# POS5V.net
KiCad netlist of a schematic drawn in Altium Designer
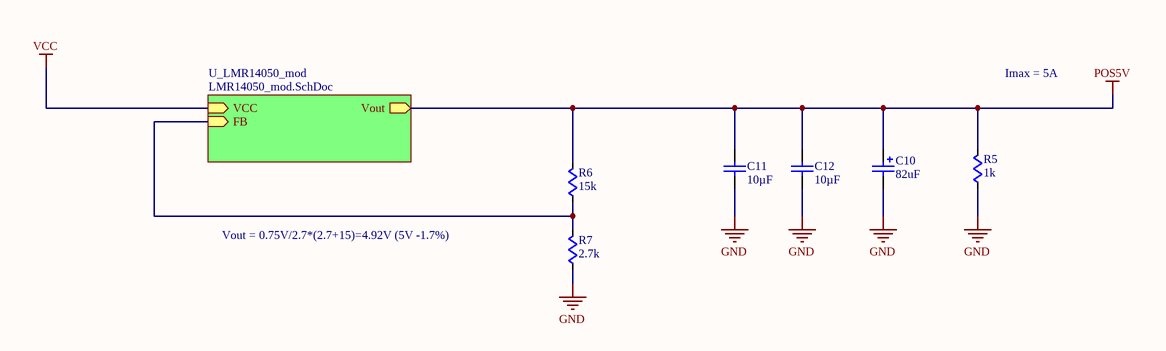
[diagram p0: POS5V.SchDoc]

(export (version "E")
  (design (tool "Eeschema 10.0.6"))
  (components
    (comp (ref "C10")
      (value "82uF")
      (footprint "CAP_EEFK_D8")
      (description "Polarized Capacitor (Surface Mount)")
      (fields (field (name "MANUFACTURER_PART_NUMBER") "EEEFK1V680XP"))
      (libsource (lib "AEVC-lib") (part "EEEFK1V680XP"))
    )
    (comp (ref "C11")
      (value "10µF")
      (footprint "C0805")
      (description "capacitor")
      (fields (field (name "Comment") "Cap"))
      (libsource (lib "ChipComponents") (part "Cap"))
    )
    (comp (ref "C12")
      (value "10µF")
      (footprint "C0805")
      (description "capacitor")
      (fields (field (name "Comment") "Cap"))
      (libsource (lib "ChipComponents") (part "Cap"))
    )
    (comp (ref "R5")
      (value "1k")
      (footprint "R0805")
      (description "resistor")
      (fields (field (name "Comment") "Res"))
      (libsource (lib "ChipComponents") (part "Res"))
    )
    (comp (ref "R6")
      (value "15k")
      (footprint "R0805")
      (description "resistor")
      (fields (field (name "Comment") "Res"))
      (libsource (lib "ChipComponents") (part "Res"))
    )
    (comp (ref "R7")
      (value "2.7k")
      (footprint "R0805")
      (description "resistor")
      (fields (field (name "Comment") "Res"))
      (libsource (lib "ChipComponents") (part "Res"))
    )
  )
  (nets
    (net (code "1") (name "/FB") (class "Default")
      (node (ref "R6") (pin "1") (pinfunction "1_1") (pintype "passive"))
      (node (ref "R7") (pin "2") (pinfunction "2_2") (pintype "passive"))
    )
    (net (code "2") (name "GND") (class "Default")
      (node (ref "C10") (pin "2") (pinfunction "2_2") (pintype "passive"))
      (node (ref "C11") (pin "1") (pinfunction "1_1") (pintype "passive"))
      (node (ref "C12") (pin "1") (pinfunction "1_1") (pintype "passive"))
      (node (ref "R5") (pin "1") (pinfunction "1_1") (pintype "passive"))
      (node (ref "R7") (pin "1") (pinfunction "1_1") (pintype "passive"))
    )
    (net (code "3") (name "POS5V") (class "Default")
      (node (ref "C10") (pin "1") (pinfunction "1_1") (pintype "passive"))
      (node (ref "C11") (pin "2") (pinfunction "2_2") (pintype "passive"))
      (node (ref "C12") (pin "2") (pinfunction "2_2") (pintype "passive"))
      (node (ref "R5") (pin "2") (pinfunction "2_2") (pintype "passive"))
      (node (ref "R6") (pin "2") (pinfunction "2_2") (pintype "passive"))
    )
  )
)
